# ETH-PHY.net
KiCad netlist of a schematic drawn in Altium Designer
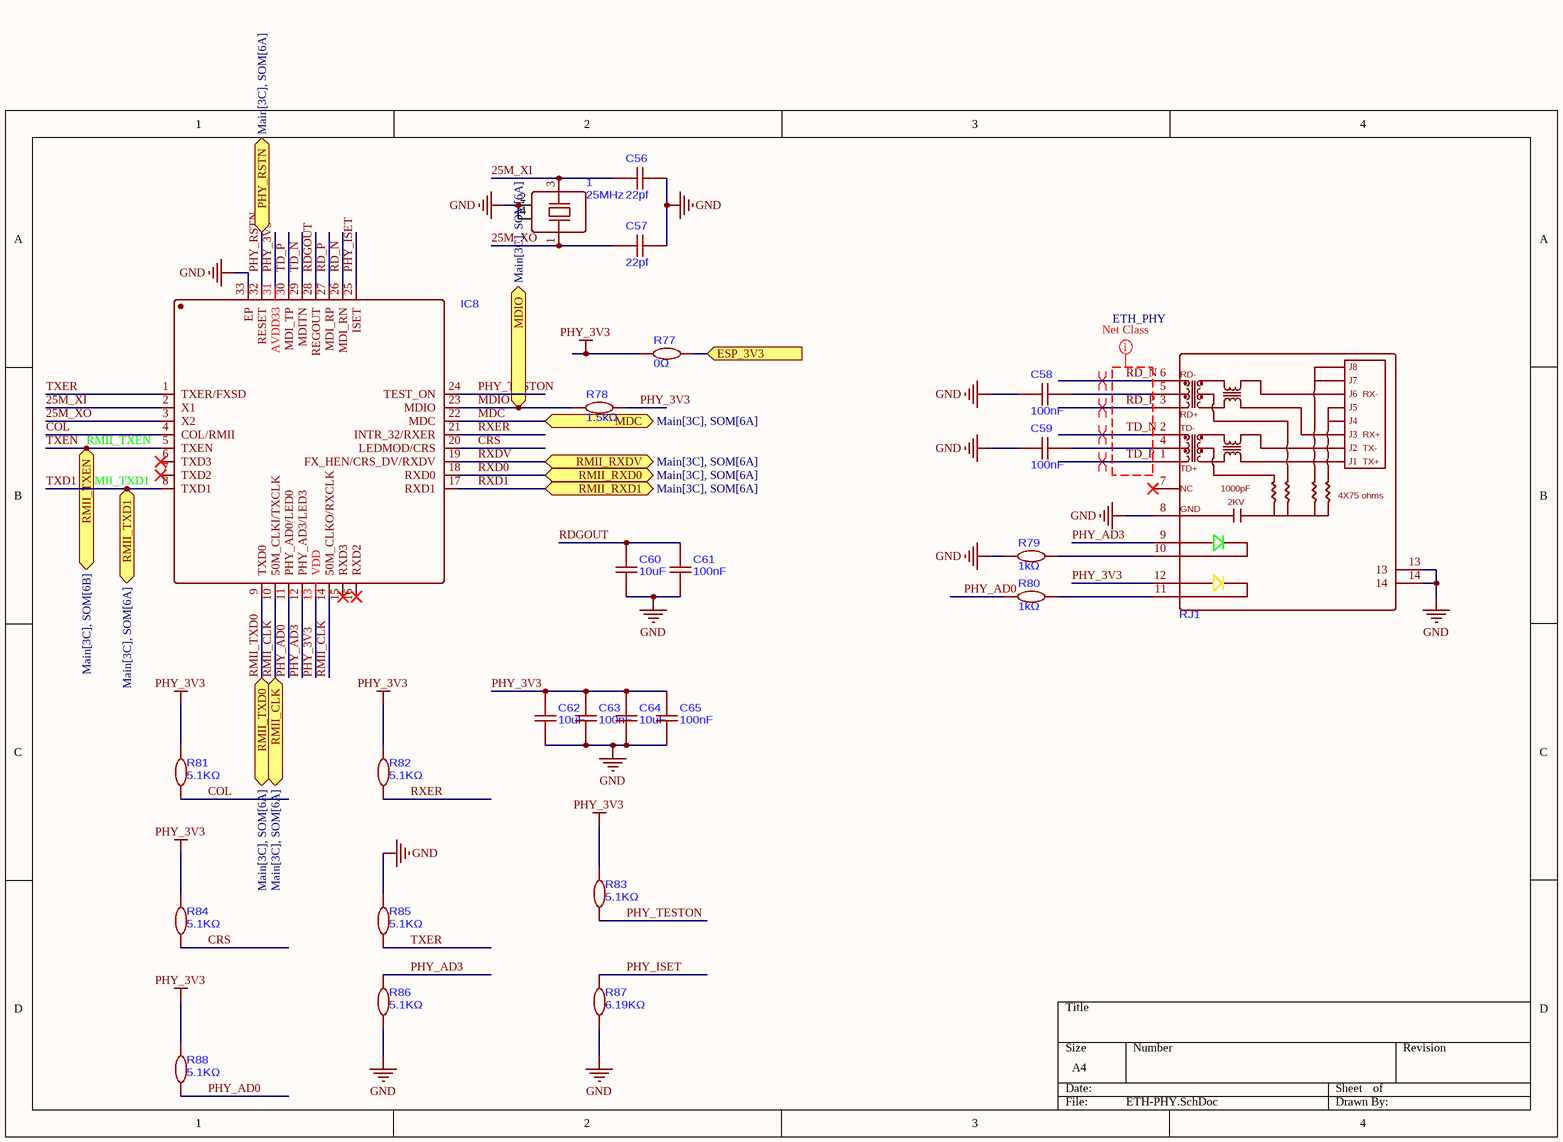
[diagram p0: ETH-PHY.SchDoc]

(export (version "E")
  (design (tool "Eeschema 10.0.6"))
  (components
    (comp (ref "1")
      (value "25MHz")
      (footprint "CRYSTAL-SMD_4P-L3.2-W2.5-BL")
      (libsource (lib "Schlib2") (part "X322525MOB4SI"))
    )
    (comp (ref "C56")
      (value "22pf")
      (footprint "C0603")
      (description "50V 22pF C0G ±5% 0603 Ceramic Capacitors RoHS")
      (libsource (lib "Schlib2") (part "CL10C220JB8NNNC"))
    )
    (comp (ref "C57")
      (value "22pf")
      (footprint "C0603")
      (description "50V 22pF C0G ±5% 0603 Ceramic Capacitors RoHS")
      (libsource (lib "Schlib2") (part "CL10C220JB8NNNC"))
    )
    (comp (ref "C58")
      (value "100nF")
      (footprint "C0603")
      (description "50V 100nF X7R ±10% 0603 Ceramic Capacitors ROHS")
      (libsource (lib "Schlib2") (part "CC0603KRX7R9BB104"))
    )
    (comp (ref "C59")
      (value "100nF")
      (footprint "C0603")
      (description "50V 100nF X7R ±10% 0603 Ceramic Capacitors ROHS")
      (libsource (lib "Schlib2") (part "CC0603KRX7R9BB104"))
    )
    (comp (ref "C60")
      (value "10uF")
      (footprint "C0603")
      (description "25V 10uF X5R ±20% 0603 Ceramic Capacitors ROHS")
      (libsource (lib "Schlib2") (part "CL10A106MA8NRNC"))
    )
    (comp (ref "C61")
      (value "100nF")
      (footprint "C0603")
      (description "50V 100nF X7R ±10% 0603 Ceramic Capacitors ROHS")
      (libsource (lib "Schlib2") (part "CC0603KRX7R9BB104"))
    )
    (comp (ref "C62")
      (value "10uF")
      (footprint "C0603")
      (description "25V 10uF X5R ±20% 0603 Ceramic Capacitors ROHS")
      (libsource (lib "Schlib2") (part "CL10A106MA8NRNC"))
    )
    (comp (ref "C63")
      (value "100nF")
      (footprint "C0603")
      (description "50V 100nF X7R ±10% 0603 Ceramic Capacitors ROHS")
      (libsource (lib "Schlib2") (part "CC0603KRX7R9BB104"))
    )
    (comp (ref "C64")
      (value "10uF")
      (footprint "C0603")
      (description "25V 10uF X5R ±20% 0603 Ceramic Capacitors ROHS")
      (libsource (lib "Schlib2") (part "CL10A106MA8NRNC"))
    )
    (comp (ref "C65")
      (value "100nF")
      (footprint "C0603")
      (description "50V 100nF X7R ±10% 0603 Ceramic Capacitors ROHS")
      (libsource (lib "Schlib2") (part "CC0603KRX7R9BB104"))
    )
    (comp (ref "IC8")
      (value "Single Port Fast Ethernet Transceiver")
      (footprint "QFN-32_L4.0-W4.0-P0.40-BL-EP2.7")
      (description "Ethernet Transceiver 3.3V QFN-32-EP(4x4) Drivers, Receivers, Transceivers RoHS")
      (libsource (lib "Schlib2") (part "IP101GRI"))
    )
    (comp (ref "R77")
      (value "0Ω")
      (footprint "R0603")
      (description "100mW 0Ω 75V Thick Film Resistor ±5% 0603 Chip Resistor - Surface Mount RoHS")
      (libsource (lib "Schlib2") (part "RC0603JR-070RL"))
    )
    (comp (ref "R78")
      (value "1.5kΩ")
      (footprint "R0603")
      (description "100mW 1.5kΩ 75V ±100ppm/℃ Thick Film Resistor ±1% 0603 Chip Resistor - Surface Mount RoHS")
      (libsource (lib "Schlib2") (part "RC0603FR-071K5L"))
    )
    (comp (ref "R79")
      (value "1kΩ")
      (footprint "R0603")
      (description "100mW 1kΩ 50V ±100ppm/℃ Thick Film Resistor ±5% 0603 Chip Resistor - Surface Mount ROHS")
      (libsource (lib "Schlib2") (part "RMC 0603 1K J N"))
    )
    (comp (ref "R80")
      (value "1kΩ")
      (footprint "R0603")
      (description "100mW 1kΩ 50V ±100ppm/℃ Thick Film Resistor ±5% 0603 Chip Resistor - Surface Mount ROHS")
      (libsource (lib "Schlib2") (part "RMC 0603 1K J N"))
    )
    (comp (ref "R81")
      (value "5.1KΩ")
      (footprint "R0603")
      (description "100mW 5.1kΩ 75V ±100ppm/℃ Thick Film Resistor ±1% 0603 Chip Resistor - Surface Mount RoHS")
      (libsource (lib "Schlib2") (part "FRC0603F5101TS"))
    )
    (comp (ref "R82")
      (value "5.1KΩ")
      (footprint "R0603")
      (description "100mW 5.1kΩ 75V ±100ppm/℃ Thick Film Resistor ±1% 0603 Chip Resistor - Surface Mount RoHS")
      (libsource (lib "Schlib2") (part "FRC0603F5101TS"))
    )
    (comp (ref "R83")
      (value "5.1KΩ")
      (footprint "R0603")
      (description "100mW 5.1kΩ 75V ±100ppm/℃ Thick Film Resistor ±1% 0603 Chip Resistor - Surface Mount RoHS")
      (libsource (lib "Schlib2") (part "FRC0603F5101TS"))
    )
    (comp (ref "R84")
      (value "5.1KΩ")
      (footprint "R0603")
      (description "100mW 5.1kΩ 75V ±100ppm/℃ Thick Film Resistor ±1% 0603 Chip Resistor - Surface Mount RoHS")
      (libsource (lib "Schlib2") (part "FRC0603F5101TS"))
    )
    (comp (ref "R85")
      (value "5.1KΩ")
      (footprint "R0603")
      (description "100mW 5.1kΩ 75V ±100ppm/℃ Thick Film Resistor ±1% 0603 Chip Resistor - Surface Mount RoHS")
      (libsource (lib "Schlib2") (part "FRC0603F5101TS"))
    )
    (comp (ref "R86")
      (value "5.1KΩ")
      (footprint "R0603")
      (description "100mW 5.1kΩ 75V ±100ppm/℃ Thick Film Resistor ±1% 0603 Chip Resistor - Surface Mount RoHS")
      (libsource (lib "Schlib2") (part "FRC0603F5101TS"))
    )
    (comp (ref "R87")
      (value "6.19KΩ")
      (footprint "R0603")
      (description "6.19kΩ 100mW 75V ±100ppm/℃ Thick Film Resistor ±1% 0603 Chip Resistor - Surface Mount RoHS")
      (libsource (lib "Schlib2") (part "AC0603FR-076K19L"))
    )
    (comp (ref "R88")
      (value "5.1KΩ")
      (footprint "R0603")
      (description "100mW 5.1kΩ 75V ±100ppm/℃ Thick Film Resistor ±1% 0603 Chip Resistor - Surface Mount RoHS")
      (libsource (lib "Schlib2") (part "FRC0603F5101TS"))
    )
    (comp (ref "RJ1")
      (value "CONN MOD JACK RJ45 TH")
      (footprint "RJ45-TH_HR913550A")
      (description "1 With LED Through Hole Modular/Ethernet Connector Jacks With Magnetics RoHS")
      (libsource (lib "Schlib2") (part "HR913550A"))
    )
  )
  (nets
    (net (code "1") (name "/25M_XI") (class "Default")
      (node (ref "1") (pin "3") (pinfunction "OSC2_3") (pintype "passive"))
      (node (ref "C56") (pin "1") (pinfunction "1_1") (pintype "passive"))
      (node (ref "IC8") (pin "2") (pinfunction "X1_2") (pintype "passive"))
    )
    (net (code "2") (name "/25M_XO") (class "Default")
      (node (ref "1") (pin "1") (pinfunction "OSC1_1") (pintype "passive"))
      (node (ref "C57") (pin "1") (pinfunction "1_1") (pintype "passive"))
      (node (ref "IC8") (pin "3") (pinfunction "X2_3") (pintype "passive"))
    )
    (net (code "3") (name "/COL") (class "Default")
      (node (ref "IC8") (pin "4") (pinfunction "COL/RMII_4") (pintype "passive"))
      (node (ref "R81") (pin "1") (pinfunction "1_1") (pintype "passive"))
    )
    (net (code "4") (name "/CRS") (class "Default")
      (node (ref "IC8") (pin "20") (pinfunction "LEDMOD/CRS_20") (pintype "passive"))
      (node (ref "R84") (pin "1") (pinfunction "1_1") (pintype "passive"))
    )
    (net (code "5") (name "/ESP_3V3") (class "Default")
      (node (ref "R77") (pin "2") (pinfunction "2_2") (pintype "passive"))
    )
    (net (code "6") (name "/MDC") (class "Default")
      (node (ref "IC8") (pin "22") (pinfunction "MDC_22") (pintype "passive"))
    )
    (net (code "7") (name "/MDIO") (class "Default")
      (node (ref "IC8") (pin "23") (pinfunction "MDIO_23") (pintype "passive"))
      (node (ref "R78") (pin "1") (pinfunction "1_1") (pintype "passive"))
    )
    (net (code "8") (name "/PHY_AD0") (class "Default")
      (node (ref "IC8") (pin "11") (pinfunction "PHY_AD0/LED0_11") (pintype "passive"))
      (node (ref "R80") (pin "1") (pinfunction "1_1") (pintype "passive"))
      (node (ref "R88") (pin "1") (pinfunction "1_1") (pintype "passive"))
    )
    (net (code "9") (name "/PHY_AD3") (class "Default")
      (node (ref "IC8") (pin "12") (pinfunction "PHY_AD3/LED3_12") (pintype "passive"))
      (node (ref "R86") (pin "1") (pinfunction "1_1") (pintype "passive"))
      (node (ref "RJ1") (pin "9") (pintype "passive"))
    )
    (net (code "10") (name "/PHY_ISET") (class "Default")
      (node (ref "IC8") (pin "25") (pinfunction "ISET_25") (pintype "passive"))
      (node (ref "R87") (pin "2") (pinfunction "2_2") (pintype "passive"))
    )
    (net (code "11") (name "/PHY_RSTN") (class "Default")
      (node (ref "IC8") (pin "32") (pinfunction "RESET_32") (pintype "passive"))
    )
    (net (code "12") (name "/PHY_TESTON") (class "Default")
      (node (ref "IC8") (pin "24") (pinfunction "TEST_ON_24") (pintype "passive"))
      (node (ref "R83") (pin "1") (pinfunction "1_1") (pintype "passive"))
    )
    (net (code "13") (name "/RDGOUT") (class "Default")
      (node (ref "C60") (pin "2") (pinfunction "2_2") (pintype "passive"))
      (node (ref "C61") (pin "2") (pinfunction "2_2") (pintype "passive"))
      (node (ref "IC8") (pin "28") (pinfunction "REGOUT_28") (pintype "passive"))
    )
    (net (code "14") (name "/RD_N") (class "Default")
      (node (ref "IC8") (pin "26") (pinfunction "MDI_RN_26") (pintype "passive"))
      (node (ref "RJ1") (pin "6") (pintype "passive"))
    )
    (net (code "15") (name "/RD_P") (class "Default")
      (node (ref "IC8") (pin "27") (pinfunction "MDI_RP_27") (pintype "passive"))
      (node (ref "RJ1") (pin "3") (pintype "passive"))
    )
    (net (code "16") (name "/RMII_CLK") (class "Default")
      (node (ref "IC8") (pin "10") (pinfunction "50M_CLKI/TXCLK_10") (pintype "passive"))
      (node (ref "IC8") (pin "14") (pinfunction "50M_CLKO/RXCLK_14") (pintype "passive"))
    )
    (net (code "17") (name "/RMII_TXD0") (class "Default")
      (node (ref "IC8") (pin "9") (pinfunction "TXD0_9") (pintype "passive"))
    )
    (net (code "18") (name "/RMII_TXD1") (class "Default")
      (node (ref "IC8") (pin "8") (pinfunction "TXD1_8") (pintype "passive"))
    )
    (net (code "19") (name "/RMII_TXEN") (class "Default")
      (node (ref "IC8") (pin "5") (pinfunction "TXEN_5") (pintype "passive"))
    )
    (net (code "20") (name "/RXD0") (class "Default")
      (node (ref "IC8") (pin "18") (pinfunction "RXD0_18") (pintype "passive"))
    )
    (net (code "21") (name "/RXD1") (class "Default")
      (node (ref "IC8") (pin "17") (pinfunction "RXD1_17") (pintype "passive"))
    )
    (net (code "22") (name "/RXDV") (class "Default")
      (node (ref "IC8") (pin "19") (pinfunction "FX_HEN/CRS_DV/RXDV_19") (pintype "passive"))
    )
    (net (code "23") (name "/RXER") (class "Default")
      (node (ref "IC8") (pin "21") (pinfunction "INTR_32/RXER_21") (pintype "passive"))
      (node (ref "R82") (pin "1") (pinfunction "1_1") (pintype "passive"))
    )
    (net (code "24") (name "/TD_N") (class "Default")
      (node (ref "IC8") (pin "29") (pinfunction "MDITN_29") (pintype "passive"))
      (node (ref "RJ1") (pin "2") (pintype "passive"))
    )
    (net (code "25") (name "/TD_P") (class "Default")
      (node (ref "IC8") (pin "30") (pinfunction "MDI_TP_30") (pintype "passive"))
      (node (ref "RJ1") (pin "1") (pintype "passive"))
    )
    (net (code "26") (name "/TXER") (class "Default")
      (node (ref "IC8") (pin "1") (pinfunction "TXER/FXSD_1") (pintype "passive"))
      (node (ref "R85") (pin "1") (pinfunction "1_1") (pintype "passive"))
    )
    (net (code "27") (name "GND") (class "Default")
      (node (ref "1") (pin "2") (pinfunction "GND_2") (pintype "passive"))
      (node (ref "1") (pin "4") (pinfunction "GND_4") (pintype "passive"))
      (node (ref "C56") (pin "2") (pinfunction "2_2") (pintype "passive"))
      (node (ref "C57") (pin "2") (pinfunction "2_2") (pintype "passive"))
      (node (ref "C58") (pin "1") (pinfunction "1_1") (pintype "passive"))
      (node (ref "C59") (pin "1") (pinfunction "1_1") (pintype "passive"))
      (node (ref "C60") (pin "1") (pinfunction "1_1") (pintype "passive"))
      (node (ref "C61") (pin "1") (pinfunction "1_1") (pintype "passive"))
      (node (ref "C62") (pin "1") (pinfunction "1_1") (pintype "passive"))
      (node (ref "C63") (pin "1") (pinfunction "1_1") (pintype "passive"))
      (node (ref "C64") (pin "1") (pinfunction "1_1") (pintype "passive"))
      (node (ref "C65") (pin "1") (pinfunction "1_1") (pintype "passive"))
      (node (ref "IC8") (pin "33") (pinfunction "EP_33") (pintype "passive"))
      (node (ref "R79") (pin "1") (pinfunction "1_1") (pintype "passive"))
      (node (ref "R85") (pin "2") (pinfunction "2_2") (pintype "passive"))
      (node (ref "R86") (pin "2") (pinfunction "2_2") (pintype "passive"))
      (node (ref "R87") (pin "1") (pinfunction "1_1") (pintype "passive"))
      (node (ref "RJ1") (pin "13") (pinfunction "13_13") (pintype "passive"))
      (node (ref "RJ1") (pin "14") (pinfunction "14_14") (pintype "passive"))
      (node (ref "RJ1") (pin "8") (pinfunction "GND_8") (pintype "passive"))
    )
    (net (code "28") (name "Net-(C58-Pad2)") (class "Default")
      (node (ref "C58") (pin "2") (pinfunction "2_2") (pintype "passive"))
      (node (ref "RJ1") (pin "5") (pintype "passive"))
    )
    (net (code "29") (name "Net-(C59-Pad2)") (class "Default")
      (node (ref "C59") (pin "2") (pinfunction "2_2") (pintype "passive"))
      (node (ref "RJ1") (pin "4") (pintype "passive"))
    )
    (net (code "30") (name "Net-(R79-Pad2)") (class "Default")
      (node (ref "R79") (pin "2") (pinfunction "2_2") (pintype "passive"))
      (node (ref "RJ1") (pin "10") (pintype "passive"))
    )
    (net (code "31") (name "Net-(R80-Pad2)") (class "Default")
      (node (ref "R80") (pin "2") (pinfunction "2_2") (pintype "passive"))
      (node (ref "RJ1") (pin "11") (pintype "passive"))
    )
    (net (code "32") (name "PHY_3V3") (class "Default")
      (node (ref "C62") (pin "2") (pinfunction "2_2") (pintype "passive"))
      (node (ref "C63") (pin "2") (pinfunction "2_2") (pintype "passive"))
      (node (ref "C64") (pin "2") (pinfunction "2_2") (pintype "passive"))
      (node (ref "C65") (pin "2") (pinfunction "2_2") (pintype "passive"))
      (node (ref "IC8") (pin "13") (pinfunction "VDD_13") (pintype "passive"))
      (node (ref "IC8") (pin "31") (pinfunction "AVDD33_31") (pintype "passive"))
      (node (ref "R77") (pin "1") (pinfunction "1_1") (pintype "passive"))
      (node (ref "R78") (pin "2") (pinfunction "2_2") (pintype "passive"))
      (node (ref "R81") (pin "2") (pinfunction "2_2") (pintype "passive"))
      (node (ref "R82") (pin "2") (pinfunction "2_2") (pintype "passive"))
      (node (ref "R83") (pin "2") (pinfunction "2_2") (pintype "passive"))
      (node (ref "R84") (pin "2") (pinfunction "2_2") (pintype "passive"))
      (node (ref "R88") (pin "2") (pinfunction "2_2") (pintype "passive"))
      (node (ref "RJ1") (pin "12") (pintype "passive"))
    )
    (net (code "33") (name "unconnected-(IC8-RXD2-Pad16)") (class "Default")
      (node (ref "IC8") (pin "16") (pinfunction "RXD2_16") (pintype "passive+no_connect"))
    )
    (net (code "34") (name "unconnected-(IC8-RXD3-Pad15)") (class "Default")
      (node (ref "IC8") (pin "15") (pinfunction "RXD3_15") (pintype "passive+no_connect"))
    )
    (net (code "35") (name "unconnected-(IC8-TXD2-Pad7)") (class "Default")
      (node (ref "IC8") (pin "7") (pinfunction "TXD2_7") (pintype "passive+no_connect"))
    )
    (net (code "36") (name "unconnected-(IC8-TXD3-Pad6)") (class "Default")
      (node (ref "IC8") (pin "6") (pinfunction "TXD3_6") (pintype "passive+no_connect"))
    )
    (net (code "37") (name "unconnected-(RJ1-NC-Pad7)") (class "Default")
      (node (ref "RJ1") (pin "7") (pinfunction "NC_7") (pintype "passive+no_connect"))
    )
  )
)
